# high_power_motorshield_v1.net
KiCad netlist of a schematic drawn in EAGLE
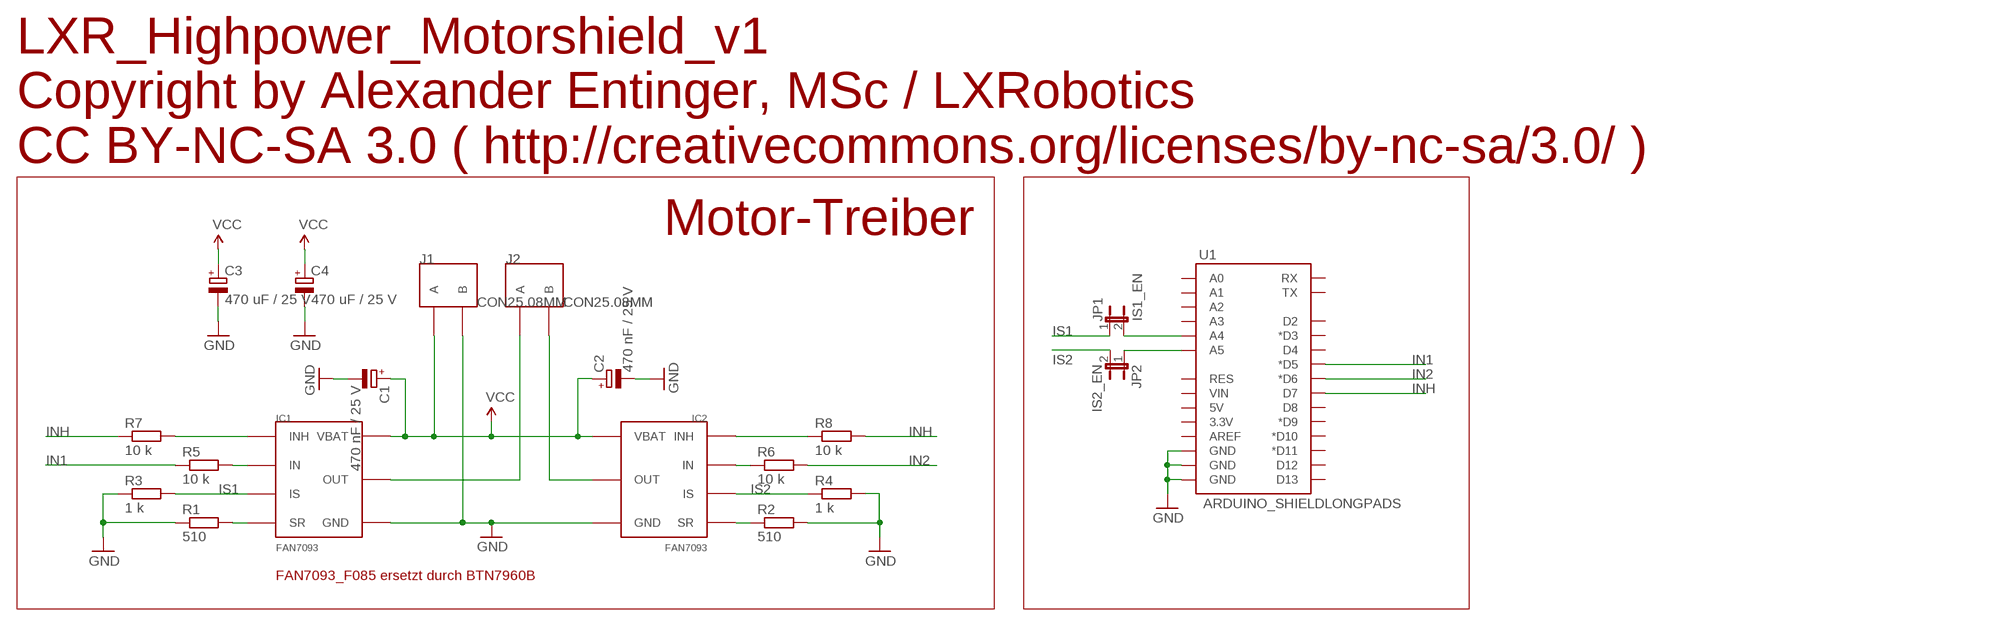
[diagram p0: schematic, sheet 1]

(export (version "E")
  (design (tool "Eeschema 10.0.6"))
  (components
    (comp (ref "C1")
      (value "470 nF / 25 V")
      (footprint "eagle-import:KEMET_A")
      (libsource (lib "eagle-import") (part "CPOL-EU"))
    )
    (comp (ref "C2")
      (value "470 nF / 25 V")
      (footprint "eagle-import:KEMET_A")
      (libsource (lib "eagle-import") (part "CPOL-EU"))
    )
    (comp (ref "C3")
      (value "470 uF / 25 V")
      (footprint "eagle-import:E5-10,5")
      (libsource (lib "eagle-import") (part "CPOL-EUE5-10.5"))
    )
    (comp (ref "C4")
      (value "470 uF / 25 V")
      (footprint "eagle-import:E5-10,5")
      (libsource (lib "eagle-import") (part "CPOL-EUE5-10.5"))
    )
    (comp (ref "IC1")
      (value "FAN7093")
      (footprint "eagle-import:TO263-7L")
      (libsource (lib "eagle-import") (part "FAN7093"))
    )
    (comp (ref "IC2")
      (value "FAN7093")
      (footprint "eagle-import:TO263-7L")
      (libsource (lib "eagle-import") (part "FAN7093"))
    )
    (comp (ref "J1")
      (value "CON25.08MM")
      (footprint "eagle-import:CON2_SCHRAUBKLEMME")
      (libsource (lib "eagle-import") (part "CON25.08MM"))
    )
    (comp (ref "J2")
      (value "CON25.08MM")
      (footprint "eagle-import:CON2_SCHRAUBKLEMME")
      (libsource (lib "eagle-import") (part "CON25.08MM"))
    )
    (comp (ref "JP1")
      (value "IS1_EN")
      (footprint "eagle-import:JP1")
      (libsource (lib "eagle-import") (part "JP1E"))
    )
    (comp (ref "JP2")
      (value "IS2_EN")
      (footprint "eagle-import:JP1")
      (libsource (lib "eagle-import") (part "JP1E"))
    )
    (comp (ref "R1")
      (value "510")
      (footprint "eagle-import:R0805")
      (libsource (lib "eagle-import") (part "R-EU_R0805"))
    )
    (comp (ref "R2")
      (value "510")
      (footprint "eagle-import:R0805")
      (libsource (lib "eagle-import") (part "R-EU_R0805"))
    )
    (comp (ref "R3")
      (value "1 k")
      (footprint "eagle-import:R0805")
      (libsource (lib "eagle-import") (part "R-EU_R0805"))
    )
    (comp (ref "R4")
      (value "1 k")
      (footprint "eagle-import:R0805")
      (libsource (lib "eagle-import") (part "R-EU_R0805"))
    )
    (comp (ref "R5")
      (value "10 k")
      (footprint "eagle-import:R0805")
      (libsource (lib "eagle-import") (part "R-EU_R0805"))
    )
    (comp (ref "R6")
      (value "10 k")
      (footprint "eagle-import:R0805")
      (libsource (lib "eagle-import") (part "R-EU_R0805"))
    )
    (comp (ref "R7")
      (value "10 k")
      (footprint "eagle-import:R0805")
      (libsource (lib "eagle-import") (part "R-EU_R0805"))
    )
    (comp (ref "R8")
      (value "10 k")
      (footprint "eagle-import:R0805")
      (libsource (lib "eagle-import") (part "R-EU_R0805"))
    )
    (comp (ref "U1")
      (value "ARDUINO_SHIELDLONGPADS")
      (footprint "eagle-import:DUEMILANOVE_SHIELD_LONGPADS")
      (libsource (lib "eagle-import") (part "ARDUINO_SHIELDLONGPADS"))
    )
  )
  (nets
    (net (code "1") (name "/IN1") (class "Default")
      (node (ref "R5") (pin "1") (pinfunction "1_1") (pintype "passive"))
      (node (ref "U1") (pin "D5") (pinfunction "*D5_D5") (pintype "bidirectional"))
    )
    (net (code "2") (name "/IN2") (class "Default")
      (node (ref "R6") (pin "2") (pinfunction "2_2") (pintype "passive"))
      (node (ref "U1") (pin "D6") (pinfunction "*D6_D6") (pintype "bidirectional"))
    )
    (net (code "3") (name "/INH") (class "Default")
      (node (ref "R7") (pin "1") (pinfunction "1_1") (pintype "passive"))
      (node (ref "R8") (pin "2") (pinfunction "2_2") (pintype "passive"))
      (node (ref "U1") (pin "D7") (pinfunction "D7_D7") (pintype "bidirectional"))
    )
    (net (code "4") (name "/IS1") (class "Default")
      (node (ref "IC1") (pin "IS") (pinfunction "IS_IS") (pintype "bidirectional"))
      (node (ref "JP1") (pin "1") (pinfunction "1_1") (pintype "passive"))
      (node (ref "R3") (pin "2") (pinfunction "2_2") (pintype "passive"))
    )
    (net (code "5") (name "/IS2") (class "Default")
      (node (ref "IC2") (pin "IS") (pinfunction "IS_IS") (pintype "bidirectional"))
      (node (ref "JP2") (pin "2") (pinfunction "2_2") (pintype "passive"))
      (node (ref "R4") (pin "1") (pinfunction "1_1") (pintype "passive"))
    )
    (net (code "6") (name "GND") (class "Default")
      (node (ref "C1") (pin "CATHODE") (pinfunction "-_CATHODE") (pintype "passive"))
      (node (ref "C2") (pin "CATHODE") (pinfunction "-_CATHODE") (pintype "passive"))
      (node (ref "C3") (pin "-") (pinfunction "-_-") (pintype "passive"))
      (node (ref "C4") (pin "-") (pinfunction "-_-") (pintype "passive"))
      (node (ref "IC1") (pin "GND") (pinfunction "GND_GND") (pintype "bidirectional"))
      (node (ref "IC2") (pin "GND") (pinfunction "GND_GND") (pintype "bidirectional"))
      (node (ref "J1") (pin "2") (pinfunction "B_2") (pintype "bidirectional"))
      (node (ref "R1") (pin "1") (pinfunction "1_1") (pintype "passive"))
      (node (ref "R2") (pin "2") (pinfunction "2_2") (pintype "passive"))
      (node (ref "R3") (pin "1") (pinfunction "1_1") (pintype "passive"))
      (node (ref "R4") (pin "2") (pinfunction "2_2") (pintype "passive"))
      (node (ref "U1") (pin "GND@0") (pinfunction "GND_GND@0") (pintype "bidirectional"))
      (node (ref "U1") (pin "GND@1") (pinfunction "GND_GND@1") (pintype "bidirectional"))
      (node (ref "U1") (pin "GND@2") (pinfunction "GND_GND@2") (pintype "bidirectional"))
    )
    (net (code "7") (name "Net-(IC1-PadIN)") (class "Default")
      (node (ref "IC1") (pin "IN") (pinfunction "IN_IN") (pintype "bidirectional"))
      (node (ref "R5") (pin "2") (pinfunction "2_2") (pintype "passive"))
    )
    (net (code "8") (name "Net-(IC1-PadINH)") (class "Default")
      (node (ref "IC1") (pin "INH") (pinfunction "INH_INH") (pintype "bidirectional"))
      (node (ref "R7") (pin "2") (pinfunction "2_2") (pintype "passive"))
    )
    (net (code "9") (name "Net-(IC1-PadSR)") (class "Default")
      (node (ref "IC1") (pin "SR") (pinfunction "SR_SR") (pintype "bidirectional"))
      (node (ref "R1") (pin "2") (pinfunction "2_2") (pintype "passive"))
    )
    (net (code "10") (name "Net-(IC2-PadIN)") (class "Default")
      (node (ref "IC2") (pin "IN") (pinfunction "IN_IN") (pintype "bidirectional"))
      (node (ref "R6") (pin "1") (pinfunction "1_1") (pintype "passive"))
    )
    (net (code "11") (name "Net-(IC2-PadINH)") (class "Default")
      (node (ref "IC2") (pin "INH") (pinfunction "INH_INH") (pintype "bidirectional"))
      (node (ref "R8") (pin "1") (pinfunction "1_1") (pintype "passive"))
    )
    (net (code "12") (name "Net-(IC2-PadSR)") (class "Default")
      (node (ref "IC2") (pin "SR") (pinfunction "SR_SR") (pintype "bidirectional"))
      (node (ref "R2") (pin "1") (pinfunction "1_1") (pintype "passive"))
    )
    (net (code "13") (name "Net-(J2-A)") (class "Default")
      (node (ref "IC1") (pin "OUT") (pinfunction "OUT_OUT") (pintype "bidirectional"))
      (node (ref "IC1") (pin "OUT@1") (pinfunction "OUT_OUT@1") (pintype "bidirectional"))
      (node (ref "J2") (pin "1") (pinfunction "A_1") (pintype "bidirectional"))
    )
    (net (code "14") (name "Net-(J2-B)") (class "Default")
      (node (ref "IC2") (pin "OUT") (pinfunction "OUT_OUT") (pintype "bidirectional"))
      (node (ref "IC2") (pin "OUT@1") (pinfunction "OUT_OUT@1") (pintype "bidirectional"))
      (node (ref "J2") (pin "2") (pinfunction "B_2") (pintype "bidirectional"))
    )
    (net (code "15") (name "Net-(JP1-Pad2)") (class "Default")
      (node (ref "JP1") (pin "2") (pinfunction "2_2") (pintype "passive"))
      (node (ref "U1") (pin "A4") (pinfunction "A4_A4") (pintype "bidirectional"))
    )
    (net (code "16") (name "Net-(JP2-Pad1)") (class "Default")
      (node (ref "JP2") (pin "1") (pinfunction "1_1") (pintype "passive"))
      (node (ref "U1") (pin "A5") (pinfunction "A5_A5") (pintype "bidirectional"))
    )
    (net (code "17") (name "VCC") (class "Default")
      (node (ref "C1") (pin "ANODE") (pinfunction "+_ANODE") (pintype "passive"))
      (node (ref "C2") (pin "ANODE") (pinfunction "+_ANODE") (pintype "passive"))
      (node (ref "C3") (pin "+") (pinfunction "+_+") (pintype "passive"))
      (node (ref "C4") (pin "+") (pinfunction "+_+") (pintype "passive"))
      (node (ref "IC1") (pin "VBATT") (pinfunction "VBAT_VBATT") (pintype "bidirectional"))
      (node (ref "IC2") (pin "VBATT") (pinfunction "VBAT_VBATT") (pintype "bidirectional"))
      (node (ref "J1") (pin "1") (pinfunction "A_1") (pintype "bidirectional"))
    )
    (net (code "18") (name "unconnected-(U1-*D3-PadD3)") (class "Default")
      (node (ref "U1") (pin "D3") (pinfunction "*D3_D3") (pintype "bidirectional"))
    )
    (net (code "19") (name "unconnected-(U1-*D9-PadD9)") (class "Default")
      (node (ref "U1") (pin "D9") (pinfunction "*D9_D9") (pintype "bidirectional"))
    )
    (net (code "20") (name "unconnected-(U1-*D10-PadD10)") (class "Default")
      (node (ref "U1") (pin "D10") (pinfunction "*D10_D10") (pintype "bidirectional"))
    )
    (net (code "21") (name "unconnected-(U1-*D11-PadD11)") (class "Default")
      (node (ref "U1") (pin "D11") (pinfunction "*D11_D11") (pintype "bidirectional"))
    )
    (net (code "22") (name "unconnected-(U1-Pad3.3V)") (class "Default")
      (node (ref "U1") (pin "3.3V") (pinfunction "3.3V_3.3V") (pintype "bidirectional"))
    )
    (net (code "23") (name "unconnected-(U1-Pad5V)") (class "Default")
      (node (ref "U1") (pin "5V") (pinfunction "5V_5V") (pintype "bidirectional"))
    )
    (net (code "24") (name "unconnected-(U1-PadA0)") (class "Default")
      (node (ref "U1") (pin "A0") (pinfunction "A0_A0") (pintype "bidirectional"))
    )
    (net (code "25") (name "unconnected-(U1-PadA1)") (class "Default")
      (node (ref "U1") (pin "A1") (pinfunction "A1_A1") (pintype "bidirectional"))
    )
    (net (code "26") (name "unconnected-(U1-PadA2)") (class "Default")
      (node (ref "U1") (pin "A2") (pinfunction "A2_A2") (pintype "bidirectional"))
    )
    (net (code "27") (name "unconnected-(U1-PadA3)") (class "Default")
      (node (ref "U1") (pin "A3") (pinfunction "A3_A3") (pintype "bidirectional"))
    )
    (net (code "28") (name "unconnected-(U1-PadAREF)") (class "Default")
      (node (ref "U1") (pin "AREF") (pinfunction "AREF_AREF") (pintype "bidirectional"))
    )
    (net (code "29") (name "unconnected-(U1-PadD2)") (class "Default")
      (node (ref "U1") (pin "D2") (pinfunction "D2_D2") (pintype "bidirectional"))
    )
    (net (code "30") (name "unconnected-(U1-PadD4)") (class "Default")
      (node (ref "U1") (pin "D4") (pinfunction "D4_D4") (pintype "bidirectional"))
    )
    (net (code "31") (name "unconnected-(U1-PadD8)") (class "Default")
      (node (ref "U1") (pin "D8") (pinfunction "D8_D8") (pintype "bidirectional"))
    )
    (net (code "32") (name "unconnected-(U1-PadD12)") (class "Default")
      (node (ref "U1") (pin "D12") (pinfunction "D12_D12") (pintype "bidirectional"))
    )
    (net (code "33") (name "unconnected-(U1-PadD13)") (class "Default")
      (node (ref "U1") (pin "D13") (pinfunction "D13_D13") (pintype "bidirectional"))
    )
    (net (code "34") (name "unconnected-(U1-PadRES)") (class "Default")
      (node (ref "U1") (pin "RES") (pinfunction "RES_RES") (pintype "bidirectional"))
    )
    (net (code "35") (name "unconnected-(U1-PadRX)") (class "Default")
      (node (ref "U1") (pin "RX") (pinfunction "RX_RX") (pintype "bidirectional"))
    )
    (net (code "36") (name "unconnected-(U1-PadTX)") (class "Default")
      (node (ref "U1") (pin "TX") (pinfunction "TX_TX") (pintype "bidirectional"))
    )
    (net (code "37") (name "unconnected-(U1-PadVIN)") (class "Default")
      (node (ref "U1") (pin "VIN") (pinfunction "VIN_VIN") (pintype "bidirectional"))
    )
  )
)
